# Gate.net
KiCad netlist of a schematic drawn in Altium Designer
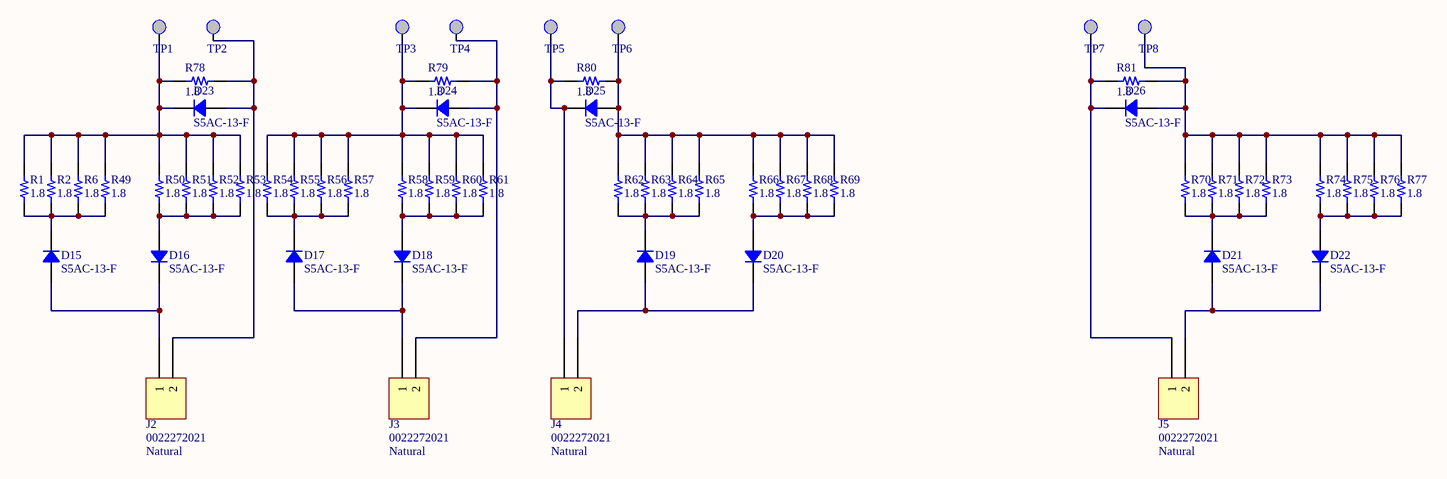
[diagram p0: Gate.SchDoc]

(export (version "E")
  (design (tool "Eeschema 10.0.6"))
  (components
    (comp (ref "D15")
      (value "S5AC-13-F")
      (footprint "DO214AB SMC")
      (description "DIODE GEN PURP 50V 5A SMC")
      (fields (field (name "MANUFACTURER") "Diodes Incorporated"))
      (libsource (lib "Celestial Library Database") (part "Diode"))
    )
    (comp (ref "D16")
      (value "S5AC-13-F")
      (footprint "DO214AB SMC")
      (description "DIODE GEN PURP 50V 5A SMC")
      (fields (field (name "MANUFACTURER") "Diodes Incorporated"))
      (libsource (lib "Celestial Library Database") (part "Diode"))
    )
    (comp (ref "D17")
      (value "S5AC-13-F")
      (footprint "DO214AB SMC")
      (description "DIODE GEN PURP 50V 5A SMC")
      (fields (field (name "MANUFACTURER") "Diodes Incorporated"))
      (libsource (lib "Celestial Library Database") (part "Diode"))
    )
    (comp (ref "D18")
      (value "S5AC-13-F")
      (footprint "DO214AB SMC")
      (description "DIODE GEN PURP 50V 5A SMC")
      (fields (field (name "MANUFACTURER") "Diodes Incorporated"))
      (libsource (lib "Celestial Library Database") (part "Diode"))
    )
    (comp (ref "D19")
      (value "S5AC-13-F")
      (footprint "DO214AB SMC")
      (description "DIODE GEN PURP 50V 5A SMC")
      (fields (field (name "MANUFACTURER") "Diodes Incorporated"))
      (libsource (lib "Celestial Library Database") (part "Diode"))
    )
    (comp (ref "D20")
      (value "S5AC-13-F")
      (footprint "DO214AB SMC")
      (description "DIODE GEN PURP 50V 5A SMC")
      (fields (field (name "MANUFACTURER") "Diodes Incorporated"))
      (libsource (lib "Celestial Library Database") (part "Diode"))
    )
    (comp (ref "D21")
      (value "S5AC-13-F")
      (footprint "DO214AB SMC")
      (description "DIODE GEN PURP 50V 5A SMC")
      (fields (field (name "MANUFACTURER") "Diodes Incorporated"))
      (libsource (lib "Celestial Library Database") (part "Diode"))
    )
    (comp (ref "D22")
      (value "S5AC-13-F")
      (footprint "DO214AB SMC")
      (description "DIODE GEN PURP 50V 5A SMC")
      (fields (field (name "MANUFACTURER") "Diodes Incorporated"))
      (libsource (lib "Celestial Library Database") (part "Diode"))
    )
    (comp (ref "D23")
      (value "S5AC-13-F")
      (footprint "DO214AB SMC")
      (description "DIODE GEN PURP 50V 5A SMC")
      (fields (field (name "MANUFACTURER") "Diodes Incorporated"))
      (libsource (lib "Celestial Library Database") (part "Diode"))
    )
    (comp (ref "D24")
      (value "S5AC-13-F")
      (footprint "DO214AB SMC")
      (description "DIODE GEN PURP 50V 5A SMC")
      (fields (field (name "MANUFACTURER") "Diodes Incorporated"))
      (libsource (lib "Celestial Library Database") (part "Diode"))
    )
    (comp (ref "D25")
      (value "S5AC-13-F")
      (footprint "DO214AB SMC")
      (description "DIODE GEN PURP 50V 5A SMC")
      (fields (field (name "MANUFACTURER") "Diodes Incorporated"))
      (libsource (lib "Celestial Library Database") (part "Diode"))
    )
    (comp (ref "D26")
      (value "S5AC-13-F")
      (footprint "DO214AB SMC")
      (description "DIODE GEN PURP 50V 5A SMC")
      (fields (field (name "MANUFACTURER") "Diodes Incorporated"))
      (libsource (lib "Celestial Library Database") (part "Diode"))
    )
    (comp (ref "J2")
      (value "0022272021")
      (footprint "MOLEX KK 0022272021")
      (description "CONN HEADER 2POS .100 VERT TIN")
      (fields (field (name "COLOUR") "Natural") (field (name "MANUFACTURER") "Molex, LLC"))
      (libsource (lib "Celestial Library Database") (part "2 Pin"))
    )
    (comp (ref "J3")
      (value "0022272021")
      (footprint "MOLEX KK 0022272021")
      (description "CONN HEADER 2POS .100 VERT TIN")
      (fields (field (name "COLOUR") "Natural") (field (name "MANUFACTURER") "Molex, LLC"))
      (libsource (lib "Celestial Library Database") (part "2 Pin"))
    )
    (comp (ref "J4")
      (value "0022272021")
      (footprint "MOLEX KK 0022272021")
      (description "CONN HEADER 2POS .100 VERT TIN")
      (fields (field (name "COLOUR") "Natural") (field (name "MANUFACTURER") "Molex, LLC"))
      (libsource (lib "Celestial Library Database") (part "2 Pin"))
    )
    (comp (ref "J5")
      (value "0022272021")
      (footprint "MOLEX KK 0022272021")
      (description "CONN HEADER 2POS .100 VERT TIN")
      (fields (field (name "COLOUR") "Natural") (field (name "MANUFACTURER") "Molex, LLC"))
      (libsource (lib "Celestial Library Database") (part "2 Pin"))
    )
    (comp (ref "R1")
      (value "1.8")
      (footprint "RES 1206/3216")
      (description "RES SMD 1.8 OHM 5% 1/4W 1206")
      (fields
        (field (name "PART NUMBER") "ERJ-8GEYJ1R8V")
        (field (name "MANUFACTURER") "Panasonic Electronic Components")
      )
      (libsource (lib "Celestial Library Database") (part "Resistor"))
    )
    (comp (ref "R2")
      (value "1.8")
      (footprint "RES 1206/3216")
      (description "RES SMD 1.8 OHM 5% 1/4W 1206")
      (fields
        (field (name "PART NUMBER") "ERJ-8GEYJ1R8V")
        (field (name "MANUFACTURER") "Panasonic Electronic Components")
      )
      (libsource (lib "Celestial Library Database") (part "Resistor"))
    )
    (comp (ref "R6")
      (value "1.8")
      (footprint "RES 1206/3216")
      (description "RES SMD 1.8 OHM 5% 1/4W 1206")
      (fields
        (field (name "PART NUMBER") "ERJ-8GEYJ1R8V")
        (field (name "MANUFACTURER") "Panasonic Electronic Components")
      )
      (libsource (lib "Celestial Library Database") (part "Resistor"))
    )
    (comp (ref "R49")
      (value "1.8")
      (footprint "RES 1206/3216")
      (description "RES SMD 1.8 OHM 5% 1/4W 1206")
      (fields
        (field (name "PART NUMBER") "ERJ-8GEYJ1R8V")
        (field (name "MANUFACTURER") "Panasonic Electronic Components")
      )
      (libsource (lib "Celestial Library Database") (part "Resistor"))
    )
    (comp (ref "R50")
      (value "1.8")
      (footprint "RES 1206/3216")
      (description "RES SMD 1.8 OHM 5% 1/4W 1206")
      (fields
        (field (name "PART NUMBER") "ERJ-8GEYJ1R8V")
        (field (name "MANUFACTURER") "Panasonic Electronic Components")
      )
      (libsource (lib "Celestial Library Database") (part "Resistor"))
    )
    (comp (ref "R51")
      (value "1.8")
      (footprint "RES 1206/3216")
      (description "RES SMD 1.8 OHM 5% 1/4W 1206")
      (fields
        (field (name "PART NUMBER") "ERJ-8GEYJ1R8V")
        (field (name "MANUFACTURER") "Panasonic Electronic Components")
      )
      (libsource (lib "Celestial Library Database") (part "Resistor"))
    )
    (comp (ref "R52")
      (value "1.8")
      (footprint "RES 1206/3216")
      (description "RES SMD 1.8 OHM 5% 1/4W 1206")
      (fields
        (field (name "PART NUMBER") "ERJ-8GEYJ1R8V")
        (field (name "MANUFACTURER") "Panasonic Electronic Components")
      )
      (libsource (lib "Celestial Library Database") (part "Resistor"))
    )
    (comp (ref "R53")
      (value "1.8")
      (footprint "RES 1206/3216")
      (description "RES SMD 1.8 OHM 5% 1/4W 1206")
      (fields
        (field (name "PART NUMBER") "ERJ-8GEYJ1R8V")
        (field (name "MANUFACTURER") "Panasonic Electronic Components")
      )
      (libsource (lib "Celestial Library Database") (part "Resistor"))
    )
    (comp (ref "R54")
      (value "1.8")
      (footprint "RES 1206/3216")
      (description "RES SMD 1.8 OHM 5% 1/4W 1206")
      (fields
        (field (name "PART NUMBER") "ERJ-8GEYJ1R8V")
        (field (name "MANUFACTURER") "Panasonic Electronic Components")
      )
      (libsource (lib "Celestial Library Database") (part "Resistor"))
    )
    (comp (ref "R55")
      (value "1.8")
      (footprint "RES 1206/3216")
      (description "RES SMD 1.8 OHM 5% 1/4W 1206")
      (fields
        (field (name "PART NUMBER") "ERJ-8GEYJ1R8V")
        (field (name "MANUFACTURER") "Panasonic Electronic Components")
      )
      (libsource (lib "Celestial Library Database") (part "Resistor"))
    )
    (comp (ref "R56")
      (value "1.8")
      (footprint "RES 1206/3216")
      (description "RES SMD 1.8 OHM 5% 1/4W 1206")
      (fields
        (field (name "PART NUMBER") "ERJ-8GEYJ1R8V")
        (field (name "MANUFACTURER") "Panasonic Electronic Components")
      )
      (libsource (lib "Celestial Library Database") (part "Resistor"))
    )
    (comp (ref "R57")
      (value "1.8")
      (footprint "RES 1206/3216")
      (description "RES SMD 1.8 OHM 5% 1/4W 1206")
      (fields
        (field (name "PART NUMBER") "ERJ-8GEYJ1R8V")
        (field (name "MANUFACTURER") "Panasonic Electronic Components")
      )
      (libsource (lib "Celestial Library Database") (part "Resistor"))
    )
    (comp (ref "R58")
      (value "1.8")
      (footprint "RES 1206/3216")
      (description "RES SMD 1.8 OHM 5% 1/4W 1206")
      (fields
        (field (name "PART NUMBER") "ERJ-8GEYJ1R8V")
        (field (name "MANUFACTURER") "Panasonic Electronic Components")
      )
      (libsource (lib "Celestial Library Database") (part "Resistor"))
    )
    (comp (ref "R59")
      (value "1.8")
      (footprint "RES 1206/3216")
      (description "RES SMD 1.8 OHM 5% 1/4W 1206")
      (fields
        (field (name "PART NUMBER") "ERJ-8GEYJ1R8V")
        (field (name "MANUFACTURER") "Panasonic Electronic Components")
      )
      (libsource (lib "Celestial Library Database") (part "Resistor"))
    )
    (comp (ref "R60")
      (value "1.8")
      (footprint "RES 1206/3216")
      (description "RES SMD 1.8 OHM 5% 1/4W 1206")
      (fields
        (field (name "PART NUMBER") "ERJ-8GEYJ1R8V")
        (field (name "MANUFACTURER") "Panasonic Electronic Components")
      )
      (libsource (lib "Celestial Library Database") (part "Resistor"))
    )
    (comp (ref "R61")
      (value "1.8")
      (footprint "RES 1206/3216")
      (description "RES SMD 1.8 OHM 5% 1/4W 1206")
      (fields
        (field (name "PART NUMBER") "ERJ-8GEYJ1R8V")
        (field (name "MANUFACTURER") "Panasonic Electronic Components")
      )
      (libsource (lib "Celestial Library Database") (part "Resistor"))
    )
    (comp (ref "R62")
      (value "1.8")
      (footprint "RES 1206/3216")
      (description "RES SMD 1.8 OHM 5% 1/4W 1206")
      (fields
        (field (name "PART NUMBER") "ERJ-8GEYJ1R8V")
        (field (name "MANUFACTURER") "Panasonic Electronic Components")
      )
      (libsource (lib "Celestial Library Database") (part "Resistor"))
    )
    (comp (ref "R63")
      (value "1.8")
      (footprint "RES 1206/3216")
      (description "RES SMD 1.8 OHM 5% 1/4W 1206")
      (fields
        (field (name "PART NUMBER") "ERJ-8GEYJ1R8V")
        (field (name "MANUFACTURER") "Panasonic Electronic Components")
      )
      (libsource (lib "Celestial Library Database") (part "Resistor"))
    )
    (comp (ref "R64")
      (value "1.8")
      (footprint "RES 1206/3216")
      (description "RES SMD 1.8 OHM 5% 1/4W 1206")
      (fields
        (field (name "PART NUMBER") "ERJ-8GEYJ1R8V")
        (field (name "MANUFACTURER") "Panasonic Electronic Components")
      )
      (libsource (lib "Celestial Library Database") (part "Resistor"))
    )
    (comp (ref "R65")
      (value "1.8")
      (footprint "RES 1206/3216")
      (description "RES SMD 1.8 OHM 5% 1/4W 1206")
      (fields
        (field (name "PART NUMBER") "ERJ-8GEYJ1R8V")
        (field (name "MANUFACTURER") "Panasonic Electronic Components")
      )
      (libsource (lib "Celestial Library Database") (part "Resistor"))
    )
    (comp (ref "R66")
      (value "1.8")
      (footprint "RES 1206/3216")
      (description "RES SMD 1.8 OHM 5% 1/4W 1206")
      (fields
        (field (name "PART NUMBER") "ERJ-8GEYJ1R8V")
        (field (name "MANUFACTURER") "Panasonic Electronic Components")
      )
      (libsource (lib "Celestial Library Database") (part "Resistor"))
    )
    (comp (ref "R67")
      (value "1.8")
      (footprint "RES 1206/3216")
      (description "RES SMD 1.8 OHM 5% 1/4W 1206")
      (fields
        (field (name "PART NUMBER") "ERJ-8GEYJ1R8V")
        (field (name "MANUFACTURER") "Panasonic Electronic Components")
      )
      (libsource (lib "Celestial Library Database") (part "Resistor"))
    )
    (comp (ref "R68")
      (value "1.8")
      (footprint "RES 1206/3216")
      (description "RES SMD 1.8 OHM 5% 1/4W 1206")
      (fields
        (field (name "PART NUMBER") "ERJ-8GEYJ1R8V")
        (field (name "MANUFACTURER") "Panasonic Electronic Components")
      )
      (libsource (lib "Celestial Library Database") (part "Resistor"))
    )
    (comp (ref "R69")
      (value "1.8")
      (footprint "RES 1206/3216")
      (description "RES SMD 1.8 OHM 5% 1/4W 1206")
      (fields
        (field (name "PART NUMBER") "ERJ-8GEYJ1R8V")
        (field (name "MANUFACTURER") "Panasonic Electronic Components")
      )
      (libsource (lib "Celestial Library Database") (part "Resistor"))
    )
    (comp (ref "R70")
      (value "1.8")
      (footprint "RES 1206/3216")
      (description "RES SMD 1.8 OHM 5% 1/4W 1206")
      (fields
        (field (name "PART NUMBER") "ERJ-8GEYJ1R8V")
        (field (name "MANUFACTURER") "Panasonic Electronic Components")
      )
      (libsource (lib "Celestial Library Database") (part "Resistor"))
    )
    (comp (ref "R71")
      (value "1.8")
      (footprint "RES 1206/3216")
      (description "RES SMD 1.8 OHM 5% 1/4W 1206")
      (fields
        (field (name "PART NUMBER") "ERJ-8GEYJ1R8V")
        (field (name "MANUFACTURER") "Panasonic Electronic Components")
      )
      (libsource (lib "Celestial Library Database") (part "Resistor"))
    )
    (comp (ref "R72")
      (value "1.8")
      (footprint "RES 1206/3216")
      (description "RES SMD 1.8 OHM 5% 1/4W 1206")
      (fields
        (field (name "PART NUMBER") "ERJ-8GEYJ1R8V")
        (field (name "MANUFACTURER") "Panasonic Electronic Components")
      )
      (libsource (lib "Celestial Library Database") (part "Resistor"))
    )
    (comp (ref "R73")
      (value "1.8")
      (footprint "RES 1206/3216")
      (description "RES SMD 1.8 OHM 5% 1/4W 1206")
      (fields
        (field (name "PART NUMBER") "ERJ-8GEYJ1R8V")
        (field (name "MANUFACTURER") "Panasonic Electronic Components")
      )
      (libsource (lib "Celestial Library Database") (part "Resistor"))
    )
    (comp (ref "R74")
      (value "1.8")
      (footprint "RES 1206/3216")
      (description "RES SMD 1.8 OHM 5% 1/4W 1206")
      (fields
        (field (name "PART NUMBER") "ERJ-8GEYJ1R8V")
        (field (name "MANUFACTURER") "Panasonic Electronic Components")
      )
      (libsource (lib "Celestial Library Database") (part "Resistor"))
    )
    (comp (ref "R75")
      (value "1.8")
      (footprint "RES 1206/3216")
      (description "RES SMD 1.8 OHM 5% 1/4W 1206")
      (fields
        (field (name "PART NUMBER") "ERJ-8GEYJ1R8V")
        (field (name "MANUFACTURER") "Panasonic Electronic Components")
      )
      (libsource (lib "Celestial Library Database") (part "Resistor"))
    )
    (comp (ref "R76")
      (value "1.8")
      (footprint "RES 1206/3216")
      (description "RES SMD 1.8 OHM 5% 1/4W 1206")
      (fields
        (field (name "PART NUMBER") "ERJ-8GEYJ1R8V")
        (field (name "MANUFACTURER") "Panasonic Electronic Components")
      )
      (libsource (lib "Celestial Library Database") (part "Resistor"))
    )
    (comp (ref "R77")
      (value "1.8")
      (footprint "RES 1206/3216")
      (description "RES SMD 1.8 OHM 5% 1/4W 1206")
      (fields
        (field (name "PART NUMBER") "ERJ-8GEYJ1R8V")
        (field (name "MANUFACTURER") "Panasonic Electronic Components")
      )
      (libsource (lib "Celestial Library Database") (part "Resistor"))
    )
    (comp (ref "R78")
      (value "1.8")
      (footprint "RES 1206/3216")
      (description "RES SMD 1.8 OHM 5% 1/4W 1206")
      (fields
        (field (name "PART NUMBER") "ERJ-8GEYJ1R8V")
        (field (name "MANUFACTURER") "Panasonic Electronic Components")
      )
      (libsource (lib "Celestial Library Database") (part "Resistor"))
    )
    (comp (ref "R79")
      (value "1.8")
      (footprint "RES 1206/3216")
      (description "RES SMD 1.8 OHM 5% 1/4W 1206")
      (fields
        (field (name "PART NUMBER") "ERJ-8GEYJ1R8V")
        (field (name "MANUFACTURER") "Panasonic Electronic Components")
      )
      (libsource (lib "Celestial Library Database") (part "Resistor"))
    )
    (comp (ref "R80")
      (value "1.8")
      (footprint "RES 1206/3216")
      (description "RES SMD 1.8 OHM 5% 1/4W 1206")
      (fields
        (field (name "PART NUMBER") "ERJ-8GEYJ1R8V")
        (field (name "MANUFACTURER") "Panasonic Electronic Components")
      )
      (libsource (lib "Celestial Library Database") (part "Resistor"))
    )
    (comp (ref "R81")
      (value "1.8")
      (footprint "RES 1206/3216")
      (description "RES SMD 1.8 OHM 5% 1/4W 1206")
      (fields
        (field (name "PART NUMBER") "ERJ-8GEYJ1R8V")
        (field (name "MANUFACTURER") "Panasonic Electronic Components")
      )
      (libsource (lib "Celestial Library Database") (part "Resistor"))
    )
    (comp (ref "TP1")
      (value "Testpoint")
      (footprint "testpoint")
      (libsource (lib "UD2 CPLD") (part "Testpoint"))
    )
    (comp (ref "TP2")
      (value "Testpoint")
      (footprint "testpoint")
      (libsource (lib "UD2 CPLD") (part "Testpoint"))
    )
    (comp (ref "TP3")
      (value "Testpoint")
      (footprint "testpoint")
      (libsource (lib "UD2 CPLD") (part "Testpoint"))
    )
    (comp (ref "TP4")
      (value "Testpoint")
      (footprint "testpoint")
      (libsource (lib "UD2 CPLD") (part "Testpoint"))
    )
    (comp (ref "TP5")
      (value "Testpoint")
      (footprint "testpoint")
      (libsource (lib "UD2 CPLD") (part "Testpoint"))
    )
    (comp (ref "TP6")
      (value "Testpoint")
      (footprint "testpoint")
      (libsource (lib "UD2 CPLD") (part "Testpoint"))
    )
    (comp (ref "TP7")
      (value "Testpoint")
      (footprint "testpoint")
      (libsource (lib "UD2 CPLD") (part "Testpoint"))
    )
    (comp (ref "TP8")
      (value "Testpoint")
      (footprint "testpoint")
      (libsource (lib "UD2 CPLD") (part "Testpoint"))
    )
  )
  (nets
    (net (code "1") (name "Net-(D15-Pad1)") (class "Default")
      (node (ref "D15") (pin "1") (pinfunction "1_1") (pintype "passive"))
      (node (ref "D16") (pin "2") (pinfunction "2_2") (pintype "passive"))
      (node (ref "J2") (pin "1") (pinfunction "1_1") (pintype "passive"))
    )
    (net (code "2") (name "Net-(D15-Pad2)") (class "Default")
      (node (ref "D15") (pin "2") (pinfunction "2_2") (pintype "passive"))
      (node (ref "R1") (pin "1") (pinfunction "1_1") (pintype "passive"))
      (node (ref "R2") (pin "1") (pinfunction "1_1") (pintype "passive"))
      (node (ref "R49") (pin "1") (pinfunction "1_1") (pintype "passive"))
      (node (ref "R6") (pin "1") (pinfunction "1_1") (pintype "passive"))
    )
    (net (code "3") (name "Net-(D16-Pad1)") (class "Default")
      (node (ref "D16") (pin "1") (pinfunction "1_1") (pintype "passive"))
      (node (ref "R50") (pin "1") (pinfunction "1_1") (pintype "passive"))
      (node (ref "R51") (pin "1") (pinfunction "1_1") (pintype "passive"))
      (node (ref "R52") (pin "1") (pinfunction "1_1") (pintype "passive"))
      (node (ref "R53") (pin "1") (pinfunction "1_1") (pintype "passive"))
    )
    (net (code "4") (name "Net-(D17-Pad1)") (class "Default")
      (node (ref "D17") (pin "1") (pinfunction "1_1") (pintype "passive"))
      (node (ref "D18") (pin "2") (pinfunction "2_2") (pintype "passive"))
      (node (ref "J3") (pin "1") (pinfunction "1_1") (pintype "passive"))
    )
    (net (code "5") (name "Net-(D17-Pad2)") (class "Default")
      (node (ref "D17") (pin "2") (pinfunction "2_2") (pintype "passive"))
      (node (ref "R54") (pin "1") (pinfunction "1_1") (pintype "passive"))
      (node (ref "R55") (pin "1") (pinfunction "1_1") (pintype "passive"))
      (node (ref "R56") (pin "1") (pinfunction "1_1") (pintype "passive"))
      (node (ref "R57") (pin "1") (pinfunction "1_1") (pintype "passive"))
    )
    (net (code "6") (name "Net-(D18-Pad1)") (class "Default")
      (node (ref "D18") (pin "1") (pinfunction "1_1") (pintype "passive"))
      (node (ref "R58") (pin "1") (pinfunction "1_1") (pintype "passive"))
      (node (ref "R59") (pin "1") (pinfunction "1_1") (pintype "passive"))
      (node (ref "R60") (pin "1") (pinfunction "1_1") (pintype "passive"))
      (node (ref "R61") (pin "1") (pinfunction "1_1") (pintype "passive"))
    )
    (net (code "7") (name "Net-(D19-Pad1)") (class "Default")
      (node (ref "D19") (pin "1") (pinfunction "1_1") (pintype "passive"))
      (node (ref "D20") (pin "2") (pinfunction "2_2") (pintype "passive"))
      (node (ref "J4") (pin "2") (pinfunction "2_2") (pintype "passive"))
    )
    (net (code "8") (name "Net-(D19-Pad2)") (class "Default")
      (node (ref "D19") (pin "2") (pinfunction "2_2") (pintype "passive"))
      (node (ref "R62") (pin "1") (pinfunction "1_1") (pintype "passive"))
      (node (ref "R63") (pin "1") (pinfunction "1_1") (pintype "passive"))
      (node (ref "R64") (pin "1") (pinfunction "1_1") (pintype "passive"))
      (node (ref "R65") (pin "1") (pinfunction "1_1") (pintype "passive"))
    )
    (net (code "9") (name "Net-(D20-Pad1)") (class "Default")
      (node (ref "D20") (pin "1") (pinfunction "1_1") (pintype "passive"))
      (node (ref "R66") (pin "1") (pinfunction "1_1") (pintype "passive"))
      (node (ref "R67") (pin "1") (pinfunction "1_1") (pintype "passive"))
      (node (ref "R68") (pin "1") (pinfunction "1_1") (pintype "passive"))
      (node (ref "R69") (pin "1") (pinfunction "1_1") (pintype "passive"))
    )
    (net (code "10") (name "Net-(D21-Pad1)") (class "Default")
      (node (ref "D21") (pin "1") (pinfunction "1_1") (pintype "passive"))
      (node (ref "D22") (pin "2") (pinfunction "2_2") (pintype "passive"))
      (node (ref "J5") (pin "2") (pinfunction "2_2") (pintype "passive"))
    )
    (net (code "11") (name "Net-(D21-Pad2)") (class "Default")
      (node (ref "D21") (pin "2") (pinfunction "2_2") (pintype "passive"))
      (node (ref "R70") (pin "1") (pinfunction "1_1") (pintype "passive"))
      (node (ref "R71") (pin "1") (pinfunction "1_1") (pintype "passive"))
      (node (ref "R72") (pin "1") (pinfunction "1_1") (pintype "passive"))
      (node (ref "R73") (pin "1") (pinfunction "1_1") (pintype "passive"))
    )
    (net (code "12") (name "Net-(D22-Pad1)") (class "Default")
      (node (ref "D22") (pin "1") (pinfunction "1_1") (pintype "passive"))
      (node (ref "R74") (pin "1") (pinfunction "1_1") (pintype "passive"))
      (node (ref "R75") (pin "1") (pinfunction "1_1") (pintype "passive"))
      (node (ref "R76") (pin "1") (pinfunction "1_1") (pintype "passive"))
      (node (ref "R77") (pin "1") (pinfunction "1_1") (pintype "passive"))
    )
    (net (code "13") (name "Net-(D23-Pad1)") (class "Default")
      (node (ref "D23") (pin "1") (pinfunction "1_1") (pintype "passive"))
      (node (ref "J2") (pin "2") (pinfunction "2_2") (pintype "passive"))
      (node (ref "R78") (pin "1") (pinfunction "1_1") (pintype "passive"))
      (node (ref "TP2") (pin "1") (pinfunction "1_1") (pintype "passive"))
    )
    (net (code "14") (name "Net-(D23-Pad2)") (class "Default")
      (node (ref "D23") (pin "2") (pinfunction "2_2") (pintype "passive"))
      (node (ref "R1") (pin "2") (pinfunction "2_2") (pintype "passive"))
      (node (ref "R2") (pin "2") (pinfunction "2_2") (pintype "passive"))
      (node (ref "R49") (pin "2") (pinfunction "2_2") (pintype "passive"))
      (node (ref "R50") (pin "2") (pinfunction "2_2") (pintype "passive"))
      (node (ref "R51") (pin "2") (pinfunction "2_2") (pintype "passive"))
      (node (ref "R52") (pin "2") (pinfunction "2_2") (pintype "passive"))
      (node (ref "R53") (pin "2") (pinfunction "2_2") (pintype "passive"))
      (node (ref "R6") (pin "2") (pinfunction "2_2") (pintype "passive"))
      (node (ref "R78") (pin "2") (pinfunction "2_2") (pintype "passive"))
      (node (ref "TP1") (pin "1") (pinfunction "1_1") (pintype "passive"))
    )
    (net (code "15") (name "Net-(D24-Pad1)") (class "Default")
      (node (ref "D24") (pin "1") (pinfunction "1_1") (pintype "passive"))
      (node (ref "J3") (pin "2") (pinfunction "2_2") (pintype "passive"))
      (node (ref "R79") (pin "1") (pinfunction "1_1") (pintype "passive"))
      (node (ref "TP4") (pin "1") (pinfunction "1_1") (pintype "passive"))
    )
    (net (code "16") (name "Net-(D24-Pad2)") (class "Default")
      (node (ref "D24") (pin "2") (pinfunction "2_2") (pintype "passive"))
      (node (ref "R54") (pin "2") (pinfunction "2_2") (pintype "passive"))
      (node (ref "R55") (pin "2") (pinfunction "2_2") (pintype "passive"))
      (node (ref "R56") (pin "2") (pinfunction "2_2") (pintype "passive"))
      (node (ref "R57") (pin "2") (pinfunction "2_2") (pintype "passive"))
      (node (ref "R58") (pin "2") (pinfunction "2_2") (pintype "passive"))
      (node (ref "R59") (pin "2") (pinfunction "2_2") (pintype "passive"))
      (node (ref "R60") (pin "2") (pinfunction "2_2") (pintype "passive"))
      (node (ref "R61") (pin "2") (pinfunction "2_2") (pintype "passive"))
      (node (ref "R79") (pin "2") (pinfunction "2_2") (pintype "passive"))
      (node (ref "TP3") (pin "1") (pinfunction "1_1") (pintype "passive"))
    )
    (net (code "17") (name "Net-(D25-Pad1)") (class "Default")
      (node (ref "D25") (pin "1") (pinfunction "1_1") (pintype "passive"))
      (node (ref "R62") (pin "2") (pinfunction "2_2") (pintype "passive"))
      (node (ref "R63") (pin "2") (pinfunction "2_2") (pintype "passive"))
      (node (ref "R64") (pin "2") (pinfunction "2_2") (pintype "passive"))
      (node (ref "R65") (pin "2") (pinfunction "2_2") (pintype "passive"))
      (node (ref "R66") (pin "2") (pinfunction "2_2") (pintype "passive"))
      (node (ref "R67") (pin "2") (pinfunction "2_2") (pintype "passive"))
      (node (ref "R68") (pin "2") (pinfunction "2_2") (pintype "passive"))
      (node (ref "R69") (pin "2") (pinfunction "2_2") (pintype "passive"))
      (node (ref "R80") (pin "1") (pinfunction "1_1") (pintype "passive"))
      (node (ref "TP6") (pin "1") (pinfunction "1_1") (pintype "passive"))
    )
    (net (code "18") (name "Net-(D25-Pad2)") (class "Default")
      (node (ref "D25") (pin "2") (pinfunction "2_2") (pintype "passive"))
      (node (ref "J4") (pin "1") (pinfunction "1_1") (pintype "passive"))
      (node (ref "R80") (pin "2") (pinfunction "2_2") (pintype "passive"))
      (node (ref "TP5") (pin "1") (pinfunction "1_1") (pintype "passive"))
    )
    (net (code "19") (name "Net-(D26-Pad1)") (class "Default")
      (node (ref "D26") (pin "1") (pinfunction "1_1") (pintype "passive"))
      (node (ref "R70") (pin "2") (pinfunction "2_2") (pintype "passive"))
      (node (ref "R71") (pin "2") (pinfunction "2_2") (pintype "passive"))
      (node (ref "R72") (pin "2") (pinfunction "2_2") (pintype "passive"))
      (node (ref "R73") (pin "2") (pinfunction "2_2") (pintype "passive"))
      (node (ref "R74") (pin "2") (pinfunction "2_2") (pintype "passive"))
      (node (ref "R75") (pin "2") (pinfunction "2_2") (pintype "passive"))
      (node (ref "R76") (pin "2") (pinfunction "2_2") (pintype "passive"))
      (node (ref "R77") (pin "2") (pinfunction "2_2") (pintype "passive"))
      (node (ref "R81") (pin "1") (pinfunction "1_1") (pintype "passive"))
      (node (ref "TP8") (pin "1") (pinfunction "1_1") (pintype "passive"))
    )
    (net (code "20") (name "Net-(D26-Pad2)") (class "Default")
      (node (ref "D26") (pin "2") (pinfunction "2_2") (pintype "passive"))
      (node (ref "J5") (pin "1") (pinfunction "1_1") (pintype "passive"))
      (node (ref "R81") (pin "2") (pinfunction "2_2") (pintype "passive"))
      (node (ref "TP7") (pin "1") (pinfunction "1_1") (pintype "passive"))
    )
  )
)
